# MCU.net
KiCad netlist of a schematic drawn in Altium Designer
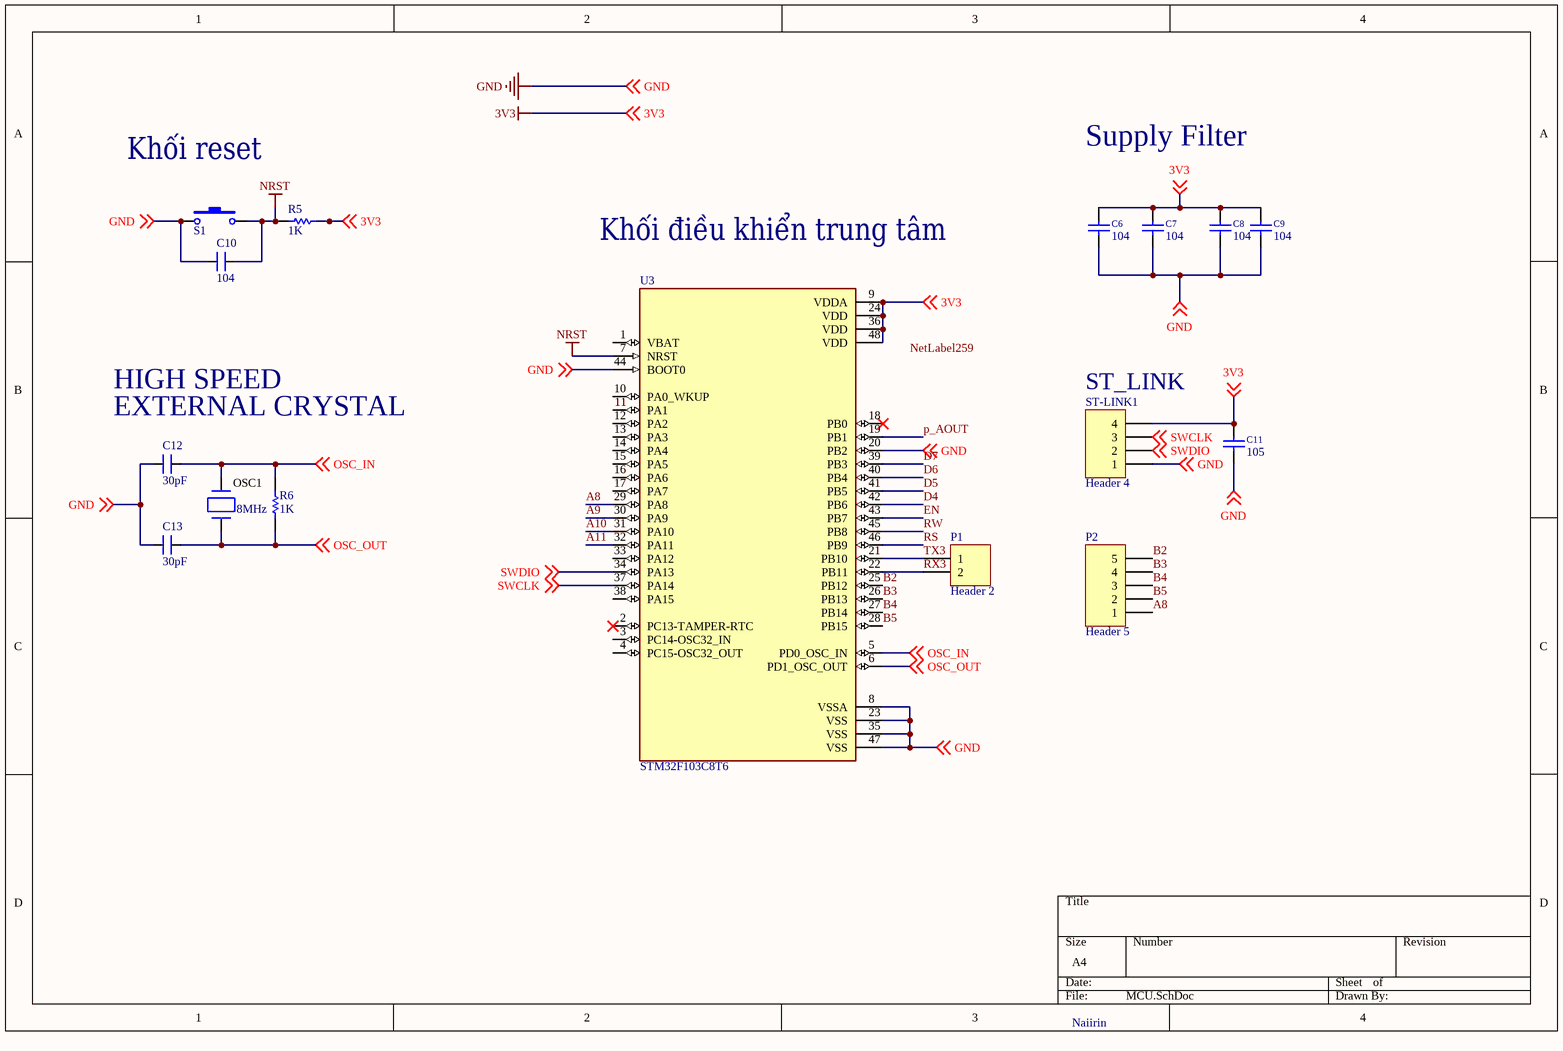
[diagram p0: MCU.SchDoc]

(export (version "E")
  (design (tool "Eeschema 10.0.6"))
  (components
    (comp (ref "C6")
      (value "104")
      (footprint "C1608-0603")
      (description "Capacitor")
      (fields (field (name "PUBLISHER") "Hoang Nguyen"))
      (libsource (lib "Kiet") (part "Capacitor"))
    )
    (comp (ref "C7")
      (value "104")
      (footprint "C1608-0603")
      (description "Capacitor")
      (fields (field (name "PUBLISHER") "Hoang Nguyen"))
      (libsource (lib "Kiet") (part "Capacitor"))
    )
    (comp (ref "C8")
      (value "104")
      (footprint "C1608-0603")
      (description "Capacitor")
      (fields (field (name "PUBLISHER") "Hoang Nguyen"))
      (libsource (lib "Kiet") (part "Capacitor"))
    )
    (comp (ref "C9")
      (value "104")
      (footprint "C1608-0603")
      (description "Capacitor")
      (fields (field (name "PUBLISHER") "Hoang Nguyen"))
      (libsource (lib "Kiet") (part "Capacitor"))
    )
    (comp (ref "C10")
      (value "104")
      (footprint "SM-0805")
      (description "Cap SMD")
      (libsource (lib "Kiet") (part "CM"))
    )
    (comp (ref "C11")
      (value "105")
      (footprint "C1608-0603")
      (description "Capacitor")
      (fields (field (name "PUBLISHER") "Hoang Nguyen"))
      (libsource (lib "Kiet") (part "Capacitor"))
    )
    (comp (ref "C12")
      (value "30pF")
      (footprint "SM-0805")
      (description "Cap SMD")
      (libsource (lib "Kiet") (part "CM"))
    )
    (comp (ref "C13")
      (value "30pF")
      (footprint "SM-0805")
      (description "Cap SMD")
      (libsource (lib "Kiet") (part "CM"))
    )
    (comp (ref "OSC1")
      (value "8MHz")
      (footprint "Crystal.HC49/USxx")
      (description "Quarz Crystal")
      (fields (field (name "Comment") "Crystal2") (field (name "PUBLISHER") "Hoang Nguyen"))
      (libsource (lib "Kiet") (part "Crystal2"))
    )
    (comp (ref "P1")
      (value "Header 2")
      (footprint "Header 2")
      (description "Header, 2-Pin")
      (fields (field (name "PUBLISHER") "Altium Limited"))
      (libsource (lib "Kiet") (part "Header 2"))
    )
    (comp (ref "P2")
      (value "Header 5")
      (footprint "Header 5")
      (description "Header, 5-Pin")
      (fields (field (name "PUBLISHER") "Altium Limited"))
      (libsource (lib "Kiet") (part "Header 5"))
    )
    (comp (ref "R5")
      (value "1K")
      (footprint "R-0805")
      (description "Resistor")
      (fields (field (name "Comment") "RESISTOR") (field (name "PUBLISHER") "Altium Limited"))
      (libsource (lib "Kiet") (part "RESISTOR"))
    )
    (comp (ref "R6")
      (value "1K")
      (footprint "R-0805")
      (description "Resistor")
      (fields (field (name "Comment") "RESISTOR") (field (name "PUBLISHER") "Altium Limited"))
      (libsource (lib "Kiet") (part "RESISTOR"))
    )
    (comp (ref "S1")
      (value "SW-SMD")
      (footprint "SW-SMD")
      (description "Switch")
      (fields (field (name "PUBLISHER") "Altium Limited"))
      (libsource (lib "Kiet") (part "SW-SMD"))
    )
    (comp (ref "ST-LINK1")
      (value "Header 4")
      (footprint "Header 4")
      (description "Header, 4-Pin")
      (fields (field (name "PUBLISHER") "Altium Limited"))
      (libsource (lib "Kiet") (part "Header 4"))
    )
    (comp (ref "U3")
      (value "STM32F103C8T6")
      (footprint "QFP50P900X900X160-48N")
      (description "ARMÂ® CortexÂ®-M3 STM32F1 Microcontroller IC 32-Bit 72MHz 64KB (64K x 8) FLASH 48-LQFP (7x7)")
      (fields (field (name "MF") "STMicroelectronics"))
      (libsource (lib "STM32F103C8T6") (part "STM32F103C8T6"))
    )
  )
  (nets
    (net (code "1") (name "/A8") (class "Default")
      (node (ref "P2") (pin "1") (pinfunction "1_1") (pintype "passive"))
      (node (ref "U3") (pin "29") (pinfunction "PA8_29") (pintype "bidirectional"))
    )
    (net (code "2") (name "/A9") (class "Default")
      (node (ref "U3") (pin "30") (pinfunction "PA9_30") (pintype "bidirectional"))
    )
    (net (code "3") (name "/A10") (class "Default")
      (node (ref "U3") (pin "31") (pinfunction "PA10_31") (pintype "bidirectional"))
    )
    (net (code "4") (name "/A11") (class "Default")
      (node (ref "U3") (pin "32") (pinfunction "PA11_32") (pintype "bidirectional"))
    )
    (net (code "5") (name "/B2") (class "Default")
      (node (ref "P2") (pin "5") (pinfunction "5_5") (pintype "passive"))
      (node (ref "U3") (pin "25") (pinfunction "PB12_25") (pintype "bidirectional"))
    )
    (net (code "6") (name "/B3") (class "Default")
      (node (ref "P2") (pin "4") (pinfunction "4_4") (pintype "passive"))
      (node (ref "U3") (pin "26") (pinfunction "PB13_26") (pintype "bidirectional"))
    )
    (net (code "7") (name "/B4") (class "Default")
      (node (ref "P2") (pin "3") (pinfunction "3_3") (pintype "passive"))
      (node (ref "U3") (pin "27") (pinfunction "PB14_27") (pintype "bidirectional"))
    )
    (net (code "8") (name "/B5") (class "Default")
      (node (ref "P2") (pin "2") (pinfunction "2_2") (pintype "passive"))
      (node (ref "U3") (pin "28") (pinfunction "PB15_28") (pintype "bidirectional"))
    )
    (net (code "9") (name "/D4") (class "Default")
      (node (ref "U3") (pin "42") (pinfunction "PB6_42") (pintype "bidirectional"))
    )
    (net (code "10") (name "/D5") (class "Default")
      (node (ref "U3") (pin "41") (pinfunction "PB5_41") (pintype "bidirectional"))
    )
    (net (code "11") (name "/D6") (class "Default")
      (node (ref "U3") (pin "40") (pinfunction "PB4_40") (pintype "bidirectional"))
    )
    (net (code "12") (name "/D7") (class "Default")
      (node (ref "U3") (pin "39") (pinfunction "PB3_39") (pintype "bidirectional"))
    )
    (net (code "13") (name "/EN") (class "Default")
      (node (ref "U3") (pin "43") (pinfunction "PB7_43") (pintype "bidirectional"))
    )
    (net (code "15") (name "/RS") (class "Default")
      (node (ref "U3") (pin "46") (pinfunction "PB9_46") (pintype "bidirectional"))
    )
    (net (code "16") (name "/RW") (class "Default")
      (node (ref "U3") (pin "45") (pinfunction "PB8_45") (pintype "bidirectional"))
    )
    (net (code "17") (name "/RX3") (class "Default")
      (node (ref "P1") (pin "2") (pinfunction "2_2") (pintype "passive"))
      (node (ref "U3") (pin "22") (pinfunction "PB11_22") (pintype "bidirectional"))
    )
    (net (code "18") (name "/TX3") (class "Default")
      (node (ref "P1") (pin "1") (pinfunction "1_1") (pintype "passive"))
      (node (ref "U3") (pin "21") (pinfunction "PB10_21") (pintype "bidirectional"))
    )
    (net (code "19") (name "/p_AOUT") (class "Default")
      (node (ref "U3") (pin "19") (pinfunction "PB1_19") (pintype "bidirectional"))
    )
    (net (code "20") (name "3V3") (class "Default")
      (node (ref "C11") (pin "2") (pinfunction "2_2") (pintype "passive"))
      (node (ref "C6") (pin "2") (pinfunction "2_2") (pintype "passive"))
      (node (ref "C7") (pin "2") (pinfunction "2_2") (pintype "passive"))
      (node (ref "C8") (pin "2") (pinfunction "2_2") (pintype "passive"))
      (node (ref "C9") (pin "2") (pinfunction "2_2") (pintype "passive"))
      (node (ref "R5") (pin "2") (pinfunction "2_2") (pintype "passive"))
      (node (ref "ST-LINK1") (pin "4") (pinfunction "4_4") (pintype "passive"))
      (node (ref "U3") (pin "24") (pinfunction "VDD_24") (pintype "power_in"))
      (node (ref "U3") (pin "36") (pinfunction "VDD_36") (pintype "power_in"))
      (node (ref "U3") (pin "48") (pinfunction "VDD_48") (pintype "power_in"))
      (node (ref "U3") (pin "9") (pinfunction "VDDA_9") (pintype "power_in"))
    )
    (net (code "21") (name "GND") (class "Default")
      (node (ref "C10") (pin "1") (pinfunction "1_1") (pintype "passive"))
      (node (ref "C11") (pin "1") (pinfunction "1_1") (pintype "passive"))
      (node (ref "C12") (pin "1") (pinfunction "1_1") (pintype "passive"))
      (node (ref "C13") (pin "1") (pinfunction "1_1") (pintype "passive"))
      (node (ref "C6") (pin "1") (pinfunction "1_1") (pintype "passive"))
      (node (ref "C7") (pin "1") (pinfunction "1_1") (pintype "passive"))
      (node (ref "C8") (pin "1") (pinfunction "1_1") (pintype "passive"))
      (node (ref "C9") (pin "1") (pinfunction "1_1") (pintype "passive"))
      (node (ref "S1") (pin "1") (pinfunction "1_1") (pintype "passive"))
      (node (ref "ST-LINK1") (pin "1") (pinfunction "1_1") (pintype "passive"))
      (node (ref "U3") (pin "20") (pinfunction "PB2_20") (pintype "bidirectional"))
      (node (ref "U3") (pin "23") (pinfunction "VSS_23") (pintype "power_in"))
      (node (ref "U3") (pin "35") (pinfunction "VSS_35") (pintype "power_in"))
      (node (ref "U3") (pin "44") (pinfunction "BOOT0_44") (pintype "input"))
      (node (ref "U3") (pin "47") (pinfunction "VSS_47") (pintype "power_in"))
      (node (ref "U3") (pin "8") (pinfunction "VSSA_8") (pintype "power_in"))
    )
    (net (code "22") (name "NRST") (class "Default")
      (node (ref "C10") (pin "2") (pinfunction "2_2") (pintype "passive"))
      (node (ref "R5") (pin "1") (pinfunction "1_1") (pintype "passive"))
      (node (ref "S1") (pin "2") (pinfunction "2_2") (pintype "passive"))
      (node (ref "U3") (pin "7") (pinfunction "NRST_7") (pintype "input"))
    )
    (net (code "23") (name "OSC_IN") (class "Default")
      (node (ref "C12") (pin "2") (pinfunction "2_2") (pintype "passive"))
      (node (ref "OSC1") (pin "1") (pinfunction "1_1") (pintype "passive"))
      (node (ref "R6") (pin "2") (pinfunction "2_2") (pintype "passive"))
      (node (ref "U3") (pin "5") (pinfunction "PD0_OSC_IN_5") (pintype "bidirectional"))
    )
    (net (code "24") (name "OSC_OUT") (class "Default")
      (node (ref "C13") (pin "2") (pinfunction "2_2") (pintype "passive"))
      (node (ref "OSC1") (pin "2") (pinfunction "2_2") (pintype "passive"))
      (node (ref "R6") (pin "1") (pinfunction "1_1") (pintype "passive"))
      (node (ref "U3") (pin "6") (pinfunction "PD1_OSC_OUT_6") (pintype "bidirectional"))
    )
    (net (code "25") (name "SWCLK") (class "Default")
      (node (ref "ST-LINK1") (pin "3") (pinfunction "3_3") (pintype "passive"))
      (node (ref "U3") (pin "37") (pinfunction "PA14_37") (pintype "bidirectional"))
    )
    (net (code "26") (name "SWDIO") (class "Default")
      (node (ref "ST-LINK1") (pin "2") (pinfunction "2_2") (pintype "passive"))
      (node (ref "U3") (pin "34") (pinfunction "PA13_34") (pintype "bidirectional"))
    )
    (net (code "27") (name "unconnected-(U3-PA0_WKUP-Pad10)") (class "Default")
      (node (ref "U3") (pin "10") (pinfunction "PA0_WKUP_10") (pintype "bidirectional"))
    )
    (net (code "28") (name "unconnected-(U3-PA1-Pad11)") (class "Default")
      (node (ref "U3") (pin "11") (pinfunction "PA1_11") (pintype "bidirectional"))
    )
    (net (code "29") (name "unconnected-(U3-PA2-Pad12)") (class "Default")
      (node (ref "U3") (pin "12") (pinfunction "PA2_12") (pintype "bidirectional"))
    )
    (net (code "30") (name "unconnected-(U3-PA3-Pad13)") (class "Default")
      (node (ref "U3") (pin "13") (pinfunction "PA3_13") (pintype "bidirectional"))
    )
    (net (code "31") (name "unconnected-(U3-PA4-Pad14)") (class "Default")
      (node (ref "U3") (pin "14") (pinfunction "PA4_14") (pintype "bidirectional"))
    )
    (net (code "32") (name "unconnected-(U3-PA5-Pad15)") (class "Default")
      (node (ref "U3") (pin "15") (pinfunction "PA5_15") (pintype "bidirectional"))
    )
    (net (code "33") (name "unconnected-(U3-PA6-Pad16)") (class "Default")
      (node (ref "U3") (pin "16") (pinfunction "PA6_16") (pintype "bidirectional"))
    )
    (net (code "34") (name "unconnected-(U3-PA7-Pad17)") (class "Default")
      (node (ref "U3") (pin "17") (pinfunction "PA7_17") (pintype "bidirectional"))
    )
    (net (code "35") (name "unconnected-(U3-PA12-Pad33)") (class "Default")
      (node (ref "U3") (pin "33") (pinfunction "PA12_33") (pintype "bidirectional"))
    )
    (net (code "36") (name "unconnected-(U3-PA15-Pad38)") (class "Default")
      (node (ref "U3") (pin "38") (pinfunction "PA15_38") (pintype "bidirectional"))
    )
    (net (code "37") (name "unconnected-(U3-PB0-Pad18)") (class "Default")
      (node (ref "U3") (pin "18") (pinfunction "PB0_18") (pintype "bidirectional+no_connect"))
    )
    (net (code "38") (name "unconnected-(U3-PC13-TAMPER-RTC-Pad2)") (class "Default")
      (node (ref "U3") (pin "2") (pinfunction "PC13-TAMPER-RTC_2") (pintype "bidirectional+no_connect"))
    )
    (net (code "39") (name "unconnected-(U3-PC14-OSC32_IN-Pad3)") (class "Default")
      (node (ref "U3") (pin "3") (pinfunction "PC14-OSC32_IN_3") (pintype "bidirectional"))
    )
    (net (code "40") (name "unconnected-(U3-PC15-OSC32_OUT-Pad4)") (class "Default")
      (node (ref "U3") (pin "4") (pinfunction "PC15-OSC32_OUT_4") (pintype "bidirectional"))
    )
    (net (code "41") (name "unconnected-(U3-VBAT-Pad1)") (class "Default")
      (node (ref "U3") (pin "1") (pinfunction "VBAT_1") (pintype "bidirectional"))
    )
  )
)
